# sheet3.net
KiCad netlist of a schematic drawn in Altium Designer
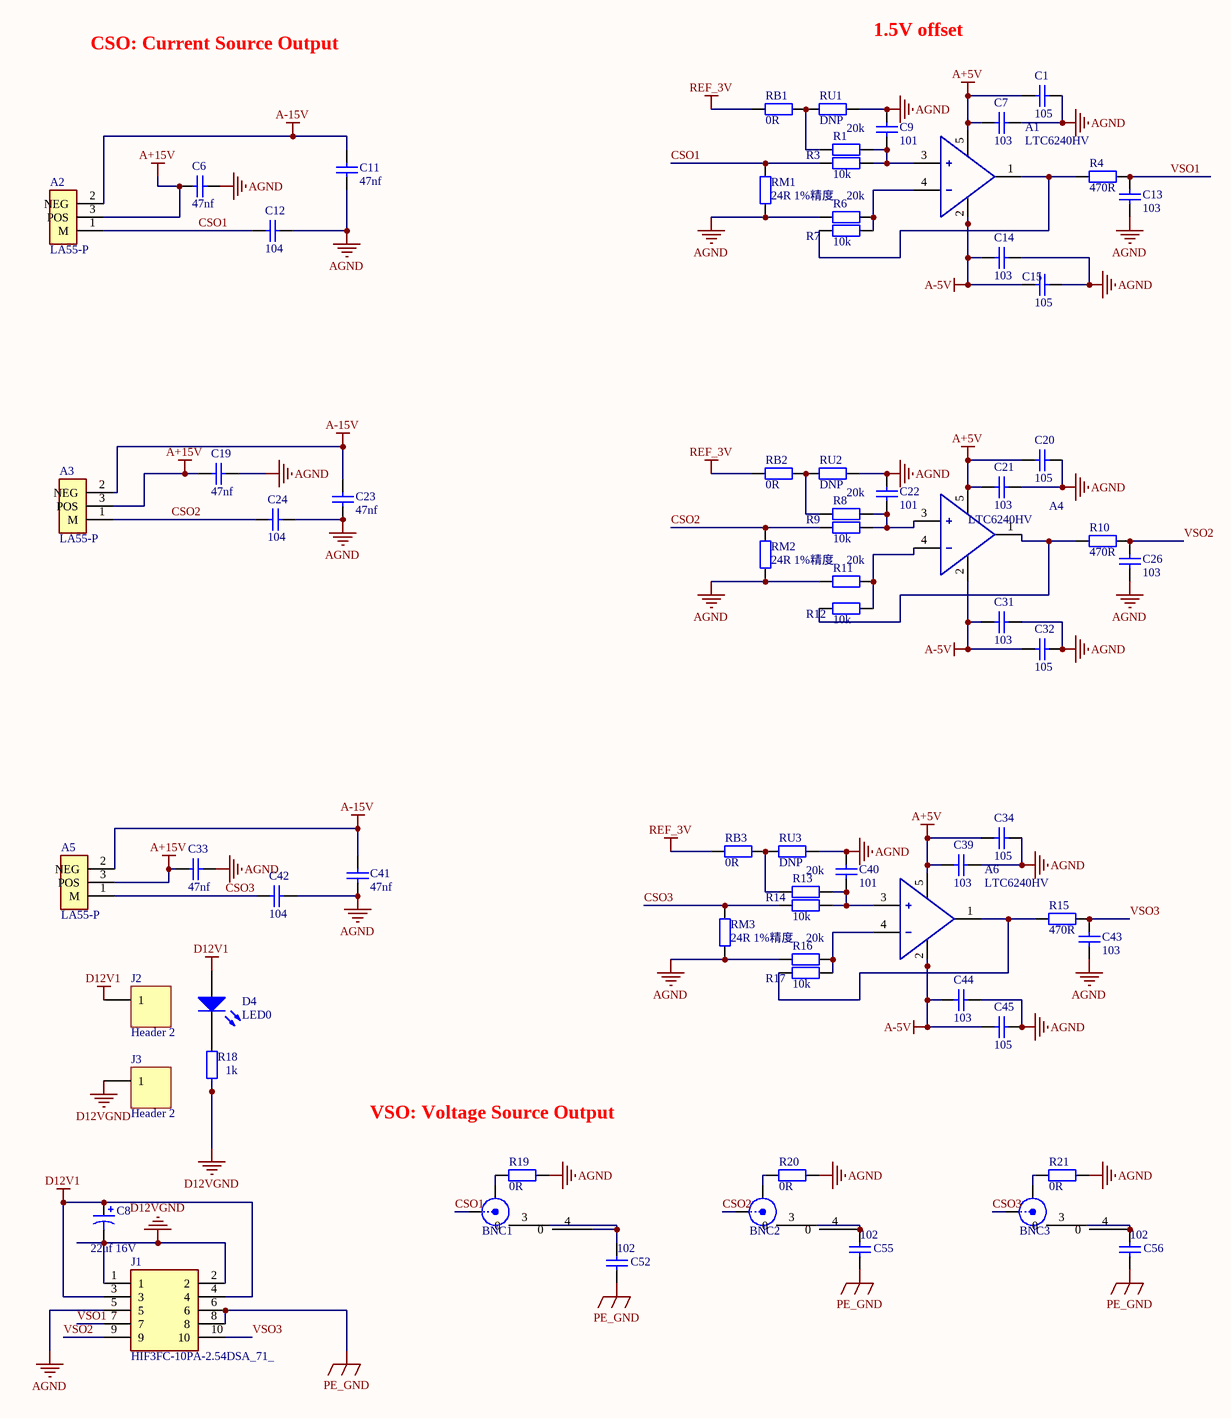
[diagram p0: sheet3.SchDoc]

(export (version "E")
  (design (tool "Eeschema 10.0.6"))
  (components
    (comp (ref "A1")
      (value "LTC6240HV")
      (footprint "SOT95P280X100-5N")
      (description "OP AMP, +-5.5V, 18MHZ, 10V/US, 5TSOT23")
      (libsource (lib "Project_Arsene") (part "AO_LTC6240HV"))
    )
    (comp (ref "A2")
      (value "LA55-P")
      (footprint "XDCR_LA55-P")
      (description "Current Sensor 50A 1 Channel Hall Effect, Closed Loop Bidirectional Module, Single Pass Through")
      (fields (field (name "MP") "LA 55-P") (field (name "MF") "LEM USA"))
      (libsource (lib "LA55-P") (part "LA55-P"))
    )
    (comp (ref "A3")
      (value "LA55-P")
      (footprint "XDCR_LA55-P")
      (description "Current Sensor 50A 1 Channel Hall Effect, Closed Loop Bidirectional Module, Single Pass Through")
      (fields (field (name "MP") "LA 55-P") (field (name "MF") "LEM USA"))
      (libsource (lib "LA55-P") (part "LA55-P"))
    )
    (comp (ref "A4")
      (value "LTC6240HV")
      (footprint "SOT95P280X100-5N")
      (description "OP AMP, +-5.5V, 18MHZ, 10V/US, 5TSOT23")
      (libsource (lib "Project_Arsene") (part "AO_LTC6240HV"))
    )
    (comp (ref "A5")
      (value "LA55-P")
      (footprint "XDCR_LA55-P")
      (description "Current Sensor 50A 1 Channel Hall Effect, Closed Loop Bidirectional Module, Single Pass Through")
      (fields (field (name "MP") "LA 55-P") (field (name "MF") "LEM USA"))
      (libsource (lib "LA55-P") (part "LA55-P"))
    )
    (comp (ref "A6")
      (value "LTC6240HV")
      (footprint "SOT95P280X100-5N")
      (description "OP AMP, +-5.5V, 18MHZ, 10V/US, 5TSOT23")
      (libsource (lib "Project_Arsene") (part "AO_LTC6240HV"))
    )
    (comp (ref "BNC1")
      (value "BNC")
      (footprint "BNC")
      (description "BNC Elbow Connector")
      (fields (field (name "PUBLISHER") "Altium Limited"))
      (libsource (lib "Miscellaneous Connectors") (part "BNC"))
    )
    (comp (ref "BNC2")
      (value "BNC")
      (footprint "BNC")
      (description "BNC Elbow Connector")
      (fields (field (name "PUBLISHER") "Altium Limited"))
      (libsource (lib "Miscellaneous Connectors") (part "BNC"))
    )
    (comp (ref "BNC3")
      (value "BNC")
      (footprint "BNC")
      (description "BNC Elbow Connector")
      (fields (field (name "PUBLISHER") "Altium Limited"))
      (libsource (lib "Miscellaneous Connectors") (part "BNC"))
    )
    (comp (ref "C1")
      (value "105")
      (footprint "0805")
      (description "Capacitor")
      (fields (field (name "PUBLISHER") "Altium Limited"))
      (libsource (lib "Miscellaneous Devices") (part "Cap"))
    )
    (comp (ref "C6")
      (value "47nf")
      (footprint "0805")
      (description "Capacitor (Semiconductor SIM Model)")
      (fields (field (name "PUBLISHER") "Altium Limited"))
      (libsource (lib "Miscellaneous Devices") (part "Cap Semi"))
    )
    (comp (ref "C7")
      (value "103")
      (footprint "0805")
      (description "Capacitor")
      (fields (field (name "PUBLISHER") "Altium Limited"))
      (libsource (lib "Miscellaneous Devices") (part "Cap"))
    )
    (comp (ref "C8")
      (value "22uf 16V")
      (footprint "1206 (钽电容)")
      (description "Polarized Capacitor (Radial)")
      (fields (field (name "PUBLISHER") "Altium Limited"))
      (libsource (lib "Miscellaneous Devices") (part "Cap Pol1"))
    )
    (comp (ref "C9")
      (value "101")
      (footprint "0805")
      (description "Capacitor")
      (fields (field (name "PUBLISHER") "Altium Limited"))
      (libsource (lib "Miscellaneous Devices") (part "Cap"))
    )
    (comp (ref "C11")
      (value "47nf")
      (footprint "0805")
      (description "Capacitor (Semiconductor SIM Model)")
      (fields (field (name "PUBLISHER") "Altium Limited"))
      (libsource (lib "Miscellaneous Devices") (part "Cap Semi"))
    )
    (comp (ref "C12")
      (value "104")
      (footprint "0805")
      (description "Capacitor (Semiconductor SIM Model)")
      (fields (field (name "PUBLISHER") "Altium Limited"))
      (libsource (lib "Miscellaneous Devices") (part "Cap Semi"))
    )
    (comp (ref "C13")
      (value "103")
      (footprint "0805")
      (description "Capacitor")
      (fields (field (name "PUBLISHER") "Altium Limited"))
      (libsource (lib "Miscellaneous Devices") (part "Cap"))
    )
    (comp (ref "C14")
      (value "103")
      (footprint "0805")
      (description "Capacitor")
      (fields (field (name "PUBLISHER") "Altium Limited"))
      (libsource (lib "Miscellaneous Devices") (part "Cap"))
    )
    (comp (ref "C15")
      (value "105")
      (footprint "0805")
      (description "Capacitor")
      (fields (field (name "PUBLISHER") "Altium Limited"))
      (libsource (lib "Miscellaneous Devices") (part "Cap"))
    )
    (comp (ref "C19")
      (value "47nf")
      (footprint "0805")
      (description "Capacitor (Semiconductor SIM Model)")
      (fields (field (name "PUBLISHER") "Altium Limited"))
      (libsource (lib "Miscellaneous Devices") (part "Cap Semi"))
    )
    (comp (ref "C20")
      (value "105")
      (footprint "0805")
      (description "Capacitor")
      (fields (field (name "PUBLISHER") "Altium Limited"))
      (libsource (lib "Miscellaneous Devices") (part "Cap"))
    )
    (comp (ref "C21")
      (value "103")
      (footprint "0805")
      (description "Capacitor")
      (fields (field (name "PUBLISHER") "Altium Limited"))
      (libsource (lib "Miscellaneous Devices") (part "Cap"))
    )
    (comp (ref "C22")
      (value "101")
      (footprint "0805")
      (description "Capacitor")
      (fields (field (name "PUBLISHER") "Altium Limited"))
      (libsource (lib "Miscellaneous Devices") (part "Cap"))
    )
    (comp (ref "C23")
      (value "47nf")
      (footprint "0805")
      (description "Capacitor (Semiconductor SIM Model)")
      (fields (field (name "PUBLISHER") "Altium Limited"))
      (libsource (lib "Miscellaneous Devices") (part "Cap Semi"))
    )
    (comp (ref "C24")
      (value "104")
      (footprint "0805")
      (description "Capacitor (Semiconductor SIM Model)")
      (fields (field (name "PUBLISHER") "Altium Limited"))
      (libsource (lib "Miscellaneous Devices") (part "Cap Semi"))
    )
    (comp (ref "C26")
      (value "103")
      (footprint "0805")
      (description "Capacitor")
      (fields (field (name "PUBLISHER") "Altium Limited"))
      (libsource (lib "Miscellaneous Devices") (part "Cap"))
    )
    (comp (ref "C31")
      (value "103")
      (footprint "0805")
      (description "Capacitor")
      (fields (field (name "PUBLISHER") "Altium Limited"))
      (libsource (lib "Miscellaneous Devices") (part "Cap"))
    )
    (comp (ref "C32")
      (value "105")
      (footprint "0805")
      (description "Capacitor")
      (fields (field (name "PUBLISHER") "Altium Limited"))
      (libsource (lib "Miscellaneous Devices") (part "Cap"))
    )
    (comp (ref "C33")
      (value "47nf")
      (footprint "0805")
      (description "Capacitor (Semiconductor SIM Model)")
      (fields (field (name "PUBLISHER") "Altium Limited"))
      (libsource (lib "Miscellaneous Devices") (part "Cap Semi"))
    )
    (comp (ref "C34")
      (value "105")
      (footprint "0805")
      (description "Capacitor")
      (fields (field (name "PUBLISHER") "Altium Limited"))
      (libsource (lib "Miscellaneous Devices") (part "Cap"))
    )
    (comp (ref "C39")
      (value "103")
      (footprint "0805")
      (description "Capacitor")
      (fields (field (name "PUBLISHER") "Altium Limited"))
      (libsource (lib "Miscellaneous Devices") (part "Cap"))
    )
    (comp (ref "C40")
      (value "101")
      (footprint "0805")
      (description "Capacitor")
      (fields (field (name "PUBLISHER") "Altium Limited"))
      (libsource (lib "Miscellaneous Devices") (part "Cap"))
    )
    (comp (ref "C41")
      (value "47nf")
      (footprint "0805")
      (description "Capacitor (Semiconductor SIM Model)")
      (fields (field (name "PUBLISHER") "Altium Limited"))
      (libsource (lib "Miscellaneous Devices") (part "Cap Semi"))
    )
    (comp (ref "C42")
      (value "104")
      (footprint "0805")
      (description "Capacitor (Semiconductor SIM Model)")
      (fields (field (name "PUBLISHER") "Altium Limited"))
      (libsource (lib "Miscellaneous Devices") (part "Cap Semi"))
    )
    (comp (ref "C43")
      (value "103")
      (footprint "0805")
      (description "Capacitor")
      (fields (field (name "PUBLISHER") "Altium Limited"))
      (libsource (lib "Miscellaneous Devices") (part "Cap"))
    )
    (comp (ref "C44")
      (value "103")
      (footprint "0805")
      (description "Capacitor")
      (fields (field (name "PUBLISHER") "Altium Limited"))
      (libsource (lib "Miscellaneous Devices") (part "Cap"))
    )
    (comp (ref "C45")
      (value "105")
      (footprint "0805")
      (description "Capacitor")
      (fields (field (name "PUBLISHER") "Altium Limited"))
      (libsource (lib "Miscellaneous Devices") (part "Cap"))
    )
    (comp (ref "C52")
      (value "102")
      (footprint "0805")
      (description "Capacitor (Semiconductor SIM Model)")
      (fields (field (name "PUBLISHER") "Altium Limited"))
      (libsource (lib "Miscellaneous Devices") (part "Cap Semi"))
    )
    (comp (ref "C55")
      (value "102")
      (footprint "0805")
      (description "Capacitor (Semiconductor SIM Model)")
      (fields (field (name "PUBLISHER") "Altium Limited"))
      (libsource (lib "Miscellaneous Devices") (part "Cap Semi"))
    )
    (comp (ref "C56")
      (value "102")
      (footprint "0805")
      (description "Capacitor (Semiconductor SIM Model)")
      (fields (field (name "PUBLISHER") "Altium Limited"))
      (libsource (lib "Miscellaneous Devices") (part "Cap Semi"))
    )
    (comp (ref "D4")
      (value "LED0")
      (footprint "l0805")
      (description "Typical INFRARED GaAs LED")
      (fields (field (name "PUBLISHER") "Altium Limited"))
      (libsource (lib "Miscellaneous Devices") (part "LED0"))
    )
    (comp (ref "J1")
      (value "HIF3FC-10PA-2.54DSA_71_")
      (footprint "Project_Oshinoko:SHDR10W50P254_2X5_2020X850X920P")
      (description "Connector")
      (fields
        (field (name "MANUFACTURER_PART_NUMBER") "HIF3FC-10PA-2.54DSA(71)")
        (field (name "MOUSER PART NUMBER") "798-HIF3FC10PA254D71")
      )
      (libsource (lib "*") (part "HIF3FC-10PA-2.54DSA_71_"))
    )
    (comp (ref "J2")
      (value "Header 2")
      (footprint "接地柱M3")
      (description "Header, 2-Pin")
      (fields (field (name "PUBLISHER") "Altium Limited"))
      (libsource (lib "Project_Oshinoko") (part "Header 2_1"))
    )
    (comp (ref "J3")
      (value "Header 2")
      (footprint "接地柱M3")
      (description "Header, 2-Pin")
      (fields (field (name "PUBLISHER") "Altium Limited"))
      (libsource (lib "Project_Oshinoko") (part "Header 2_1"))
    )
    (comp (ref "R1")
      (value "20k")
      (footprint "0805")
      (description "Resistor")
      (fields (field (name "PUBLISHER") "Altium Limited"))
      (libsource (lib "Miscellaneous Devices") (part "Res2"))
    )
    (comp (ref "R3")
      (value "10k")
      (footprint "0805")
      (description "Resistor")
      (fields (field (name "PUBLISHER") "Altium Limited"))
      (libsource (lib "Miscellaneous Devices") (part "Res2"))
    )
    (comp (ref "R4")
      (value "470R")
      (footprint "0805")
      (description "Resistor")
      (fields (field (name "PUBLISHER") "Altium Limited"))
      (libsource (lib "") (part "Res2_1"))
    )
    (comp (ref "R6")
      (value "20k")
      (footprint "0805")
      (description "Resistor")
      (fields (field (name "PUBLISHER") "Altium Limited"))
      (libsource (lib "Miscellaneous Devices") (part "Res2"))
    )
    (comp (ref "R7")
      (value "10k")
      (footprint "0805")
      (description "Resistor")
      (fields (field (name "PUBLISHER") "Altium Limited"))
      (libsource (lib "Miscellaneous Devices") (part "Res2"))
    )
    (comp (ref "R8")
      (value "20k")
      (footprint "0805")
      (description "Resistor")
      (fields (field (name "PUBLISHER") "Altium Limited"))
      (libsource (lib "Miscellaneous Devices") (part "Res2"))
    )
    (comp (ref "R9")
      (value "10k")
      (footprint "0805")
      (description "Resistor")
      (fields (field (name "PUBLISHER") "Altium Limited"))
      (libsource (lib "Miscellaneous Devices") (part "Res2"))
    )
    (comp (ref "R10")
      (value "470R")
      (footprint "0805")
      (description "Resistor")
      (fields (field (name "PUBLISHER") "Altium Limited"))
      (libsource (lib "") (part "Res2_1"))
    )
    (comp (ref "R11")
      (value "20k")
      (footprint "0805")
      (description "Resistor")
      (fields (field (name "PUBLISHER") "Altium Limited"))
      (libsource (lib "Miscellaneous Devices") (part "Res2"))
    )
    (comp (ref "R12")
      (value "10k")
      (footprint "0805")
      (description "Resistor")
      (fields (field (name "PUBLISHER") "Altium Limited"))
      (libsource (lib "Miscellaneous Devices") (part "Res2"))
    )
    (comp (ref "R13")
      (value "20k")
      (footprint "0805")
      (description "Resistor")
      (fields (field (name "PUBLISHER") "Altium Limited"))
      (libsource (lib "Miscellaneous Devices") (part "Res2"))
    )
    (comp (ref "R14")
      (value "10k")
      (footprint "0805")
      (description "Resistor")
      (fields (field (name "PUBLISHER") "Altium Limited"))
      (libsource (lib "Miscellaneous Devices") (part "Res2"))
    )
    (comp (ref "R15")
      (value "470R")
      (footprint "0805")
      (description "Resistor")
      (fields (field (name "PUBLISHER") "Altium Limited"))
      (libsource (lib "") (part "Res2_1"))
    )
    (comp (ref "R16")
      (value "20k")
      (footprint "0805")
      (description "Resistor")
      (fields (field (name "PUBLISHER") "Altium Limited"))
      (libsource (lib "Miscellaneous Devices") (part "Res2"))
    )
    (comp (ref "R17")
      (value "10k")
      (footprint "0805")
      (description "Resistor")
      (fields (field (name "PUBLISHER") "Altium Limited"))
      (libsource (lib "Miscellaneous Devices") (part "Res2"))
    )
    (comp (ref "R18")
      (value "1k")
      (footprint "0805")
      (description "Resistor")
      (fields (field (name "PUBLISHER") "Altium Limited"))
      (libsource (lib "") (part "Res2_3"))
    )
    (comp (ref "R19")
      (value "0R")
      (footprint "0805")
      (description "Resistor")
      (fields (field (name "PUBLISHER") "Altium Limited"))
      (libsource (lib "") (part "Res2_1"))
    )
    (comp (ref "R20")
      (value "0R")
      (footprint "0805")
      (description "Resistor")
      (fields (field (name "PUBLISHER") "Altium Limited"))
      (libsource (lib "") (part "Res2_1"))
    )
    (comp (ref "R21")
      (value "0R")
      (footprint "0805")
      (description "Resistor")
      (fields (field (name "PUBLISHER") "Altium Limited"))
      (libsource (lib "") (part "Res2_1"))
    )
    (comp (ref "RB1")
      (value "0R")
      (footprint "0805")
      (description "Resistor")
      (fields (field (name "PUBLISHER") "Altium Limited"))
      (libsource (lib "Miscellaneous Devices") (part "Res2"))
    )
    (comp (ref "RB2")
      (value "0R")
      (footprint "0805")
      (description "Resistor")
      (fields (field (name "PUBLISHER") "Altium Limited"))
      (libsource (lib "Miscellaneous Devices") (part "Res2"))
    )
    (comp (ref "RB3")
      (value "0R")
      (footprint "0805")
      (description "Resistor")
      (fields (field (name "PUBLISHER") "Altium Limited"))
      (libsource (lib "Miscellaneous Devices") (part "Res2"))
    )
    (comp (ref "RM1")
      (value "24R 1%精度")
      (footprint "2512")
      (description "Resistor")
      (fields (field (name "PUBLISHER") "Altium Limited"))
      (libsource (lib "") (part "Res2_2"))
    )
    (comp (ref "RM2")
      (value "24R 1%精度")
      (footprint "2512")
      (description "Resistor")
      (fields (field (name "PUBLISHER") "Altium Limited"))
      (libsource (lib "") (part "Res2_2"))
    )
    (comp (ref "RM3")
      (value "24R 1%精度")
      (footprint "2512")
      (description "Resistor")
      (fields (field (name "PUBLISHER") "Altium Limited"))
      (libsource (lib "") (part "Res2_2"))
    )
    (comp (ref "RU1")
      (value "DNP")
      (footprint "0805")
      (description "Resistor")
      (fields (field (name "PUBLISHER") "Altium Limited"))
      (libsource (lib "Miscellaneous Devices") (part "Res2"))
    )
    (comp (ref "RU2")
      (value "DNP")
      (footprint "0805")
      (description "Resistor")
      (fields (field (name "PUBLISHER") "Altium Limited"))
      (libsource (lib "Miscellaneous Devices") (part "Res2"))
    )
    (comp (ref "RU3")
      (value "DNP")
      (footprint "0805")
      (description "Resistor")
      (fields (field (name "PUBLISHER") "Altium Limited"))
      (libsource (lib "Miscellaneous Devices") (part "Res2"))
    )
  )
  (nets
    (net (code "1") (name "/CSO1") (class "Default")
      (node (ref "A2") (pin "1") (pinfunction "M_1") (pintype "power_in"))
      (node (ref "BNC1") (pin "1") (pinfunction "X_1") (pintype "passive"))
      (node (ref "C12") (pin "1") (pinfunction "1_1") (pintype "passive"))
      (node (ref "R3") (pin "1") (pinfunction "1_1") (pintype "passive"))
      (node (ref "RM1") (pin "1") (pinfunction "1_1") (pintype "passive"))
    )
    (net (code "2") (name "/CSO2") (class "Default")
      (node (ref "A3") (pin "1") (pinfunction "M_1") (pintype "power_in"))
      (node (ref "BNC2") (pin "1") (pinfunction "X_1") (pintype "passive"))
      (node (ref "C24") (pin "1") (pinfunction "1_1") (pintype "passive"))
      (node (ref "R9") (pin "1") (pinfunction "1_1") (pintype "passive"))
      (node (ref "RM2") (pin "1") (pinfunction "1_1") (pintype "passive"))
    )
    (net (code "3") (name "/CSO3") (class "Default")
      (node (ref "A5") (pin "1") (pinfunction "M_1") (pintype "power_in"))
      (node (ref "BNC3") (pin "1") (pinfunction "X_1") (pintype "passive"))
      (node (ref "C42") (pin "1") (pinfunction "1_1") (pintype "passive"))
      (node (ref "R14") (pin "1") (pinfunction "1_1") (pintype "passive"))
      (node (ref "RM3") (pin "1") (pinfunction "1_1") (pintype "passive"))
    )
    (net (code "4") (name "/VSO1") (class "Default")
      (node (ref "C13") (pin "2") (pinfunction "2_2") (pintype "passive"))
      (node (ref "J1") (pin "7") (pinfunction "7_7") (pintype "passive"))
      (node (ref "R4") (pin "1") (pinfunction "1_1") (pintype "passive"))
    )
    (net (code "5") (name "/VSO2") (class "Default")
      (node (ref "C26") (pin "2") (pinfunction "2_2") (pintype "passive"))
      (node (ref "J1") (pin "9") (pinfunction "9_9") (pintype "passive"))
      (node (ref "R10") (pin "1") (pinfunction "1_1") (pintype "passive"))
    )
    (net (code "6") (name "/VSO3") (class "Default")
      (node (ref "C43") (pin "2") (pinfunction "2_2") (pintype "passive"))
      (node (ref "J1") (pin "10") (pinfunction "10_10") (pintype "passive"))
      (node (ref "R15") (pin "1") (pinfunction "1_1") (pintype "passive"))
    )
    (net (code "7") (name "A+5V") (class "Default")
      (node (ref "A1") (pin "5") (pinfunction "Vcc_5") (pintype "passive"))
      (node (ref "A4") (pin "5") (pinfunction "Vcc_5") (pintype "passive"))
      (node (ref "A6") (pin "5") (pinfunction "Vcc_5") (pintype "passive"))
      (node (ref "C1") (pin "2") (pinfunction "2_2") (pintype "passive"))
      (node (ref "C20") (pin "2") (pinfunction "2_2") (pintype "passive"))
      (node (ref "C21") (pin "2") (pinfunction "2_2") (pintype "passive"))
      (node (ref "C34") (pin "2") (pinfunction "2_2") (pintype "passive"))
      (node (ref "C39") (pin "2") (pinfunction "2_2") (pintype "passive"))
      (node (ref "C7") (pin "2") (pinfunction "2_2") (pintype "passive"))
    )
    (net (code "8") (name "A+15V") (class "Default")
      (node (ref "A2") (pin "3") (pinfunction "POS_3") (pintype "power_in"))
      (node (ref "A3") (pin "3") (pinfunction "POS_3") (pintype "power_in"))
      (node (ref "A5") (pin "3") (pinfunction "POS_3") (pintype "power_in"))
      (node (ref "C19") (pin "2") (pinfunction "2_2") (pintype "passive"))
      (node (ref "C33") (pin "2") (pinfunction "2_2") (pintype "passive"))
      (node (ref "C6") (pin "2") (pinfunction "2_2") (pintype "passive"))
    )
    (net (code "9") (name "A-5V") (class "Default")
      (node (ref "A1") (pin "2") (pinfunction "Vee_2") (pintype "passive"))
      (node (ref "A4") (pin "2") (pinfunction "Vee_2") (pintype "passive"))
      (node (ref "A6") (pin "2") (pinfunction "Vee_2") (pintype "passive"))
      (node (ref "C14") (pin "2") (pinfunction "2_2") (pintype "passive"))
      (node (ref "C15") (pin "2") (pinfunction "2_2") (pintype "passive"))
      (node (ref "C31") (pin "2") (pinfunction "2_2") (pintype "passive"))
      (node (ref "C32") (pin "2") (pinfunction "2_2") (pintype "passive"))
      (node (ref "C44") (pin "2") (pinfunction "2_2") (pintype "passive"))
      (node (ref "C45") (pin "2") (pinfunction "2_2") (pintype "passive"))
    )
    (net (code "10") (name "A-15V") (class "Default")
      (node (ref "A2") (pin "2") (pinfunction "NEG_2") (pintype "power_in"))
      (node (ref "A3") (pin "2") (pinfunction "NEG_2") (pintype "power_in"))
      (node (ref "A5") (pin "2") (pinfunction "NEG_2") (pintype "power_in"))
      (node (ref "C11") (pin "2") (pinfunction "2_2") (pintype "passive"))
      (node (ref "C23") (pin "1") (pinfunction "1_1") (pintype "passive"))
      (node (ref "C41") (pin "1") (pinfunction "1_1") (pintype "passive"))
    )
    (net (code "11") (name "AGND") (class "Default")
      (node (ref "C1") (pin "1") (pinfunction "1_1") (pintype "passive"))
      (node (ref "C11") (pin "1") (pinfunction "1_1") (pintype "passive"))
      (node (ref "C12") (pin "2") (pinfunction "2_2") (pintype "passive"))
      (node (ref "C13") (pin "1") (pinfunction "1_1") (pintype "passive"))
      (node (ref "C14") (pin "1") (pinfunction "1_1") (pintype "passive"))
      (node (ref "C15") (pin "1") (pinfunction "1_1") (pintype "passive"))
      (node (ref "C19") (pin "1") (pinfunction "1_1") (pintype "passive"))
      (node (ref "C20") (pin "1") (pinfunction "1_1") (pintype "passive"))
      (node (ref "C21") (pin "1") (pinfunction "1_1") (pintype "passive"))
      (node (ref "C22") (pin "2") (pinfunction "2_2") (pintype "passive"))
      (node (ref "C23") (pin "2") (pinfunction "2_2") (pintype "passive"))
      (node (ref "C24") (pin "2") (pinfunction "2_2") (pintype "passive"))
      (node (ref "C26") (pin "1") (pinfunction "1_1") (pintype "passive"))
      (node (ref "C31") (pin "1") (pinfunction "1_1") (pintype "passive"))
      (node (ref "C32") (pin "1") (pinfunction "1_1") (pintype "passive"))
      (node (ref "C33") (pin "1") (pinfunction "1_1") (pintype "passive"))
      (node (ref "C34") (pin "1") (pinfunction "1_1") (pintype "passive"))
      (node (ref "C39") (pin "1") (pinfunction "1_1") (pintype "passive"))
      (node (ref "C40") (pin "2") (pinfunction "2_2") (pintype "passive"))
      (node (ref "C41") (pin "2") (pinfunction "2_2") (pintype "passive"))
      (node (ref "C42") (pin "2") (pinfunction "2_2") (pintype "passive"))
      (node (ref "C43") (pin "1") (pinfunction "1_1") (pintype "passive"))
      (node (ref "C44") (pin "1") (pinfunction "1_1") (pintype "passive"))
      (node (ref "C45") (pin "1") (pinfunction "1_1") (pintype "passive"))
      (node (ref "C6") (pin "1") (pinfunction "1_1") (pintype "passive"))
      (node (ref "C7") (pin "1") (pinfunction "1_1") (pintype "passive"))
      (node (ref "C9") (pin "2") (pinfunction "2_2") (pintype "passive"))
      (node (ref "J1") (pin "5") (pinfunction "5_5") (pintype "passive"))
      (node (ref "R11") (pin "1") (pinfunction "1_1") (pintype "passive"))
      (node (ref "R16") (pin "1") (pinfunction "1_1") (pintype "passive"))
      (node (ref "R19") (pin "1") (pinfunction "1_1") (pintype "passive"))
      (node (ref "R20") (pin "1") (pinfunction "1_1") (pintype "passive"))
      (node (ref "R21") (pin "1") (pinfunction "1_1") (pintype "passive"))
      (node (ref "R6") (pin "1") (pinfunction "1_1") (pintype "passive"))
      (node (ref "RM1") (pin "2") (pinfunction "2_2") (pintype "passive"))
      (node (ref "RM2") (pin "2") (pinfunction "2_2") (pintype "passive"))
      (node (ref "RM3") (pin "2") (pinfunction "2_2") (pintype "passive"))
      (node (ref "RU1") (pin "2") (pinfunction "2_2") (pintype "passive"))
      (node (ref "RU2") (pin "2") (pinfunction "2_2") (pintype "passive"))
      (node (ref "RU3") (pin "2") (pinfunction "2_2") (pintype "passive"))
    )
    (net (code "12") (name "D12V1") (class "Default")
      (node (ref "C8") (pin "1") (pinfunction "1_1") (pintype "passive"))
      (node (ref "D4") (pin "1") (pinfunction "A_1") (pintype "passive"))
      (node (ref "J1") (pin "3") (pinfunction "3_3") (pintype "passive"))
      (node (ref "J1") (pin "4") (pinfunction "4_4") (pintype "passive"))
      (node (ref "J2") (pin "1") (pinfunction "1_1") (pintype "passive"))
    )
    (net (code "13") (name "D12VGND") (class "Default")
      (node (ref "C8") (pin "2") (pinfunction "2_2") (pintype "passive"))
      (node (ref "J1") (pin "1") (pinfunction "1_1") (pintype "passive"))
      (node (ref "J1") (pin "2") (pinfunction "2_2") (pintype "passive"))
      (node (ref "J3") (pin "1") (pinfunction "1_1") (pintype "passive"))
      (node (ref "R18") (pin "1") (pinfunction "1_1") (pintype "passive"))
    )
    (net (code "14") (name "Net-(A1-+IN)") (class "Default")
      (node (ref "A1") (pin "3") (pinfunction "+IN_3") (pintype "passive"))
      (node (ref "C9") (pin "1") (pinfunction "1_1") (pintype "passive"))
      (node (ref "R1") (pin "2") (pinfunction "2_2") (pintype "passive"))
      (node (ref "R3") (pin "2") (pinfunction "2_2") (pintype "passive"))
    )
    (net (code "15") (name "Net-(A1--IN)") (class "Default")
      (node (ref "A1") (pin "4") (pinfunction "-IN_4") (pintype "passive"))
      (node (ref "R6") (pin "2") (pinfunction "2_2") (pintype "passive"))
      (node (ref "R7") (pin "2") (pinfunction "2_2") (pintype "passive"))
    )
    (net (code "16") (name "Net-(A1-out)") (class "Default")
      (node (ref "A1") (pin "1") (pinfunction "out_1") (pintype "passive"))
      (node (ref "R4") (pin "2") (pinfunction "2_2") (pintype "passive"))
      (node (ref "R7") (pin "1") (pinfunction "1_1") (pintype "passive"))
    )
    (net (code "17") (name "Net-(A4-+IN)") (class "Default")
      (node (ref "A4") (pin "3") (pinfunction "+IN_3") (pintype "passive"))
      (node (ref "C22") (pin "1") (pinfunction "1_1") (pintype "passive"))
      (node (ref "R8") (pin "2") (pinfunction "2_2") (pintype "passive"))
      (node (ref "R9") (pin "2") (pinfunction "2_2") (pintype "passive"))
    )
    (net (code "18") (name "Net-(A4--IN)") (class "Default")
      (node (ref "A4") (pin "4") (pinfunction "-IN_4") (pintype "passive"))
      (node (ref "R11") (pin "2") (pinfunction "2_2") (pintype "passive"))
      (node (ref "R12") (pin "2") (pinfunction "2_2") (pintype "passive"))
    )
    (net (code "19") (name "Net-(A4-out)") (class "Default")
      (node (ref "A4") (pin "1") (pinfunction "out_1") (pintype "passive"))
      (node (ref "R10") (pin "2") (pinfunction "2_2") (pintype "passive"))
      (node (ref "R12") (pin "1") (pinfunction "1_1") (pintype "passive"))
    )
    (net (code "20") (name "Net-(A6-+IN)") (class "Default")
      (node (ref "A6") (pin "3") (pinfunction "+IN_3") (pintype "passive"))
      (node (ref "C40") (pin "1") (pinfunction "1_1") (pintype "passive"))
      (node (ref "R13") (pin "2") (pinfunction "2_2") (pintype "passive"))
      (node (ref "R14") (pin "2") (pinfunction "2_2") (pintype "passive"))
    )
    (net (code "21") (name "Net-(A6--IN)") (class "Default")
      (node (ref "A6") (pin "4") (pinfunction "-IN_4") (pintype "passive"))
      (node (ref "R16") (pin "2") (pinfunction "2_2") (pintype "passive"))
      (node (ref "R17") (pin "2") (pinfunction "2_2") (pintype "passive"))
    )
    (net (code "22") (name "Net-(A6-out)") (class "Default")
      (node (ref "A6") (pin "1") (pinfunction "out_1") (pintype "passive"))
      (node (ref "R15") (pin "2") (pinfunction "2_2") (pintype "passive"))
      (node (ref "R17") (pin "1") (pinfunction "1_1") (pintype "passive"))
    )
    (net (code "23") (name "Net-(BNC1-0-Pad3)") (class "Default")
      (node (ref "BNC1") (pin "3") (pinfunction "0_3") (pintype "passive"))
      (node (ref "BNC1") (pin "4") (pinfunction "0_4") (pintype "passive"))
      (node (ref "C52") (pin "1") (pinfunction "1_1") (pintype "passive"))
    )
    (net (code "24") (name "Net-(BNC1-Y)") (class "Default")
      (node (ref "BNC1") (pin "2") (pinfunction "Y_2") (pintype "passive"))
      (node (ref "R19") (pin "2") (pinfunction "2_2") (pintype "passive"))
    )
    (net (code "25") (name "Net-(BNC2-0-Pad3)") (class "Default")
      (node (ref "BNC2") (pin "3") (pinfunction "0_3") (pintype "passive"))
      (node (ref "BNC2") (pin "4") (pinfunction "0_4") (pintype "passive"))
      (node (ref "C55") (pin "1") (pinfunction "1_1") (pintype "passive"))
    )
    (net (code "26") (name "Net-(BNC2-Y)") (class "Default")
      (node (ref "BNC2") (pin "2") (pinfunction "Y_2") (pintype "passive"))
      (node (ref "R20") (pin "2") (pinfunction "2_2") (pintype "passive"))
    )
    (net (code "27") (name "Net-(BNC3-0-Pad3)") (class "Default")
      (node (ref "BNC3") (pin "3") (pinfunction "0_3") (pintype "passive"))
      (node (ref "BNC3") (pin "4") (pinfunction "0_4") (pintype "passive"))
      (node (ref "C56") (pin "1") (pinfunction "1_1") (pintype "passive"))
    )
    (net (code "28") (name "Net-(BNC3-Y)") (class "Default")
      (node (ref "BNC3") (pin "2") (pinfunction "Y_2") (pintype "passive"))
      (node (ref "R21") (pin "2") (pinfunction "2_2") (pintype "passive"))
    )
    (net (code "29") (name "Net-(D4-K)") (class "Default")
      (node (ref "D4") (pin "2") (pinfunction "K_2") (pintype "passive"))
      (node (ref "R18") (pin "2") (pinfunction "2_2") (pintype "passive"))
    )
    (net (code "30") (name "Net-(R1-Pad1)") (class "Default")
      (node (ref "R1") (pin "1") (pinfunction "1_1") (pintype "passive"))
      (node (ref "RB1") (pin "2") (pinfunction "2_2") (pintype "passive"))
      (node (ref "RU1") (pin "1") (pinfunction "1_1") (pintype "passive"))
    )
    (net (code "31") (name "Net-(R8-Pad1)") (class "Default")
      (node (ref "R8") (pin "1") (pinfunction "1_1") (pintype "passive"))
      (node (ref "RB2") (pin "2") (pinfunction "2_2") (pintype "passive"))
      (node (ref "RU2") (pin "1") (pinfunction "1_1") (pintype "passive"))
    )
    (net (code "32") (name "Net-(R13-Pad1)") (class "Default")
      (node (ref "R13") (pin "1") (pinfunction "1_1") (pintype "passive"))
      (node (ref "RB3") (pin "2") (pinfunction "2_2") (pintype "passive"))
      (node (ref "RU3") (pin "1") (pinfunction "1_1") (pintype "passive"))
    )
    (net (code "33") (name "PE_GND") (class "Default")
      (node (ref "C52") (pin "2") (pinfunction "2_2") (pintype "passive"))
      (node (ref "C55") (pin "2") (pinfunction "2_2") (pintype "passive"))
      (node (ref "C56") (pin "2") (pinfunction "2_2") (pintype "passive"))
      (node (ref "J1") (pin "6") (pinfunction "6_6") (pintype "passive"))
      (node (ref "J1") (pin "8") (pinfunction "8_8") (pintype "passive"))
    )
    (net (code "34") (name "REF_3V") (class "Default")
      (node (ref "RB1") (pin "1") (pinfunction "1_1") (pintype "passive"))
      (node (ref "RB2") (pin "1") (pinfunction "1_1") (pintype "passive"))
      (node (ref "RB3") (pin "1") (pinfunction "1_1") (pintype "passive"))
    )
  )
)
